# load_cell_amp.net
KiCad netlist of a schematic drawn in Altium Designer
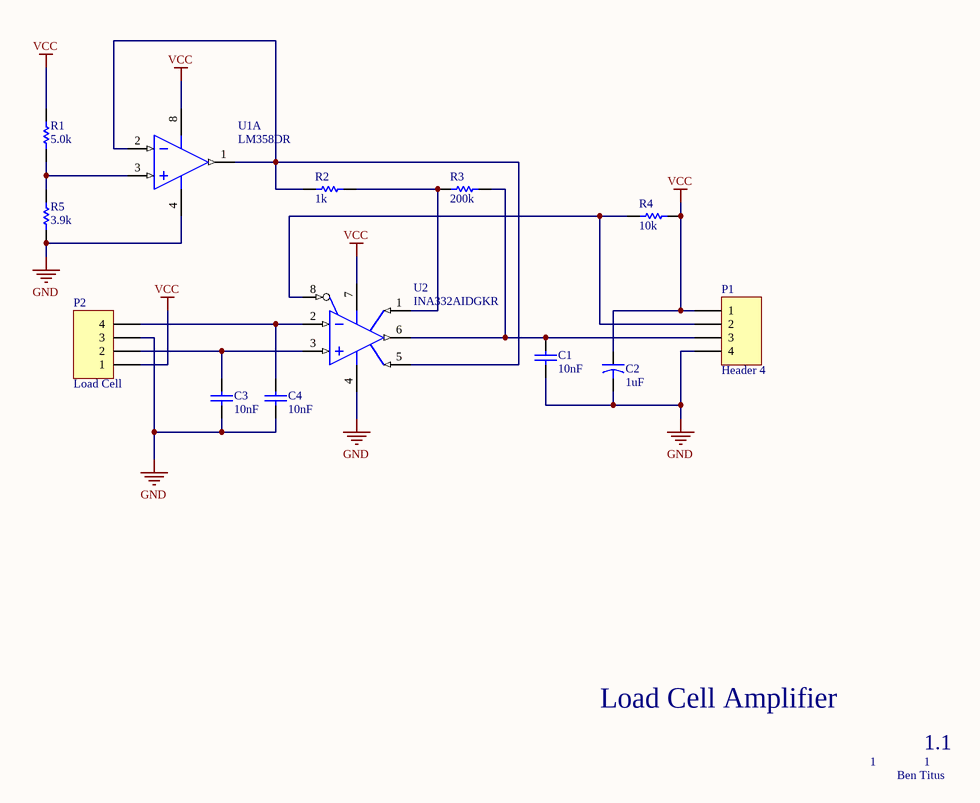
[diagram p0: load_cell_amp.SchDoc]

(export (version "E")
  (design (tool "Eeschema 10.0.6"))
  (components
    (comp (ref "C1")
      (value "10nF")
      (footprint "CAPC0805(2012)145_L")
      (description "0805 (2012 Metric) Chip Capacitor")
      (libsource (lib "Altium Content Vault") (part "CAP_5"))
    )
    (comp (ref "C2")
      (value "1uF")
      (footprint "CAPR5-4X5")
      (description "Capacitor")
      (fields (field (name "PUBLISHER") "Altium Limited"))
      (libsource (lib "Miscellaneous Devices") (part "Cap2"))
    )
    (comp (ref "C3")
      (value "10nF")
      (footprint "CAPC0805(2012)145_L")
      (description "0805 (2012 Metric) Chip Capacitor")
      (libsource (lib "Altium Content Vault") (part "CAP_5"))
    )
    (comp (ref "C4")
      (value "10nF")
      (footprint "CAPC0805(2012)145_L")
      (description "0805 (2012 Metric) Chip Capacitor")
      (libsource (lib "Altium Content Vault") (part "CAP_5"))
    )
    (comp (ref "P1")
      (value "Header 4")
      (footprint "HDR1X4")
      (description "Header, 4-Pin")
      (fields (field (name "PUBLISHER") "Altium Limited"))
      (libsource (lib "") (part "Header 4_1"))
    )
    (comp (ref "P2")
      (value "Load Cell")
      (footprint "HDR1X4")
      (description "Header, 4-Pin")
      (fields (field (name "PUBLISHER") "Altium Limited"))
      (libsource (lib "Miscellaneous Connectors") (part "Header 4"))
    )
    (comp (ref "R1")
      (value "5.0k")
      (footprint "RESC0805(2012)_L")
      (description "0805 (2012 Metric) Chip Resistor")
      (libsource (lib "Altium Content Vault") (part "RES_3"))
    )
    (comp (ref "R2")
      (value "1k")
      (footprint "RESC0805(2012)_L")
      (description "0805 (2012 Metric) Chip Resistor")
      (libsource (lib "Altium Content Vault") (part "RES_3"))
    )
    (comp (ref "R3")
      (value "200k")
      (footprint "RESC0805(2012)_L")
      (description "0805 (2012 Metric) Chip Resistor")
      (libsource (lib "Altium Content Vault") (part "RES_3"))
    )
    (comp (ref "R4")
      (value "10k")
      (footprint "RESC0805(2012)_L")
      (description "0805 (2012 Metric) Chip Resistor")
      (libsource (lib "Altium Content Vault") (part "RES_3"))
    )
    (comp (ref "R5")
      (value "3.9k")
      (footprint "RESC0805(2012)_L")
      (description "0805 (2012 Metric) Chip Resistor")
      (libsource (lib "Altium Content Vault") (part "RES_3"))
    )
    (comp (ref "U1")
      (value "LM358DR")
      (footprint "D0008A_L")
      (libsource (lib "Altium Content Vault") (part "TI-LM358-8"))
    )
    (comp (ref "U2")
      (value "INA332AIDGKR")
      (footprint "DGK0008A_M")
      (fields (field (name "MANUFACTURER") "Texas Instruments"))
      (libsource (lib "Custom_Lib") (part "CMP-0944-00077-2"))
    )
  )
  (nets
    (net (code "1") (name "GND") (class "Default")
      (node (ref "C1") (pin "1") (pinfunction "1_1") (pintype "passive"))
      (node (ref "C2") (pin "2") (pinfunction "2_2") (pintype "passive"))
      (node (ref "C3") (pin "1") (pinfunction "1_1") (pintype "passive"))
      (node (ref "C4") (pin "1") (pinfunction "1_1") (pintype "passive"))
      (node (ref "P1") (pin "4") (pinfunction "4_4") (pintype "passive"))
      (node (ref "P2") (pin "3") (pinfunction "3_3") (pintype "passive"))
      (node (ref "R5") (pin "1") (pinfunction "1_1") (pintype "passive"))
      (node (ref "U1") (pin "4") (pinfunction "GND_4") (pintype "power_in"))
      (node (ref "U2") (pin "4") (pinfunction "V-_4") (pintype "power_in"))
    )
    (net (code "2") (name "Net-(U1A-1IN+)") (class "Default")
      (node (ref "R1") (pin "1") (pinfunction "1_1") (pintype "passive"))
      (node (ref "R5") (pin "2") (pinfunction "2_2") (pintype "passive"))
      (node (ref "U1") (pin "3") (pinfunction "1IN+_3") (pintype "input"))
    )
    (net (code "3") (name "Net-(U1A-1IN-)") (class "Default")
      (node (ref "R2") (pin "1") (pinfunction "1_1") (pintype "passive"))
      (node (ref "U1") (pin "1") (pinfunction "1OUT_1") (pintype "output"))
      (node (ref "U1") (pin "2") (pinfunction "1IN-_2") (pintype "input"))
      (node (ref "U2") (pin "5") (pinfunction "REF_5") (pintype "input"))
    )
    (net (code "4") (name "Net-(U2-RG)") (class "Default")
      (node (ref "R2") (pin "2") (pinfunction "2_2") (pintype "passive"))
      (node (ref "R3") (pin "1") (pinfunction "1_1") (pintype "passive"))
      (node (ref "U2") (pin "1") (pinfunction "RG_1") (pintype "input"))
    )
    (net (code "5") (name "Net-(U2-SHUTDOWN)") (class "Default")
      (node (ref "P1") (pin "2") (pinfunction "2_2") (pintype "passive"))
      (node (ref "R4") (pin "2") (pinfunction "2_2") (pintype "passive"))
      (node (ref "U2") (pin "8") (pinfunction "SHUTDOWN_8") (pintype "input"))
    )
    (net (code "6") (name "Net-(U2-VIN+)") (class "Default")
      (node (ref "C3") (pin "2") (pinfunction "2_2") (pintype "passive"))
      (node (ref "P2") (pin "2") (pinfunction "2_2") (pintype "passive"))
      (node (ref "U2") (pin "3") (pinfunction "VIN+_3") (pintype "input"))
    )
    (net (code "7") (name "Net-(U2-VIN-)") (class "Default")
      (node (ref "C4") (pin "2") (pinfunction "2_2") (pintype "passive"))
      (node (ref "P2") (pin "4") (pinfunction "4_4") (pintype "passive"))
      (node (ref "U2") (pin "2") (pinfunction "VIN-_2") (pintype "input"))
    )
    (net (code "8") (name "Net-(U2-VOUT)") (class "Default")
      (node (ref "C1") (pin "2") (pinfunction "2_2") (pintype "passive"))
      (node (ref "P1") (pin "3") (pinfunction "3_3") (pintype "passive"))
      (node (ref "R3") (pin "2") (pinfunction "2_2") (pintype "passive"))
      (node (ref "U2") (pin "6") (pinfunction "VOUT_6") (pintype "output"))
    )
    (net (code "9") (name "VCC") (class "Default")
      (node (ref "C2") (pin "1") (pinfunction "1_1") (pintype "passive"))
      (node (ref "P1") (pin "1") (pinfunction "1_1") (pintype "passive"))
      (node (ref "P2") (pin "1") (pinfunction "1_1") (pintype "passive"))
      (node (ref "R1") (pin "2") (pinfunction "2_2") (pintype "passive"))
      (node (ref "R4") (pin "1") (pinfunction "1_1") (pintype "passive"))
      (node (ref "U1") (pin "8") (pinfunction "VCC_8") (pintype "power_in"))
      (node (ref "U2") (pin "7") (pinfunction "V+_7") (pintype "power_in"))
    )
  )
)
